# main.net
KiCad netlist of a schematic drawn in Altium Designer
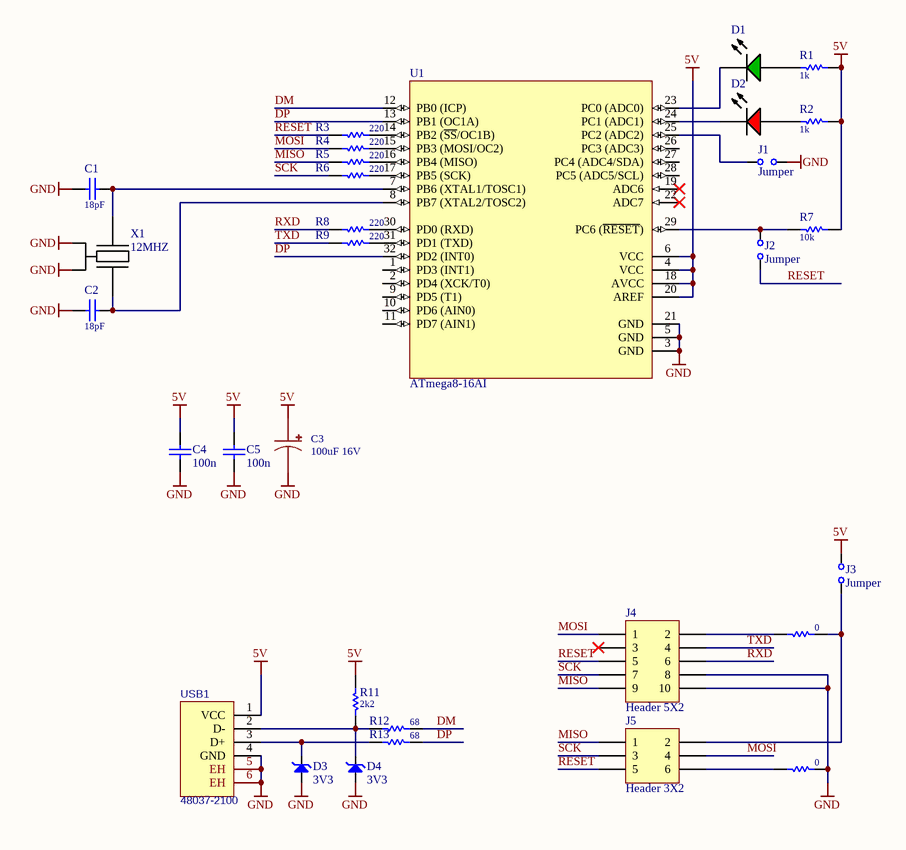
[diagram p0: main.SchDoc]

(export (version "E")
  (design (tool "Eeschema 10.0.6"))
  (components
    (comp (ref "C1")
      (value "18pF")
      (footprint "C0402")
      (description "18pF 50V 0402")
      (libsource (lib "Miscellaneous Devices") (part "CAP"))
    )
    (comp (ref "C2")
      (value "18pF")
      (footprint "C0402")
      (description "18pF 50V 0402")
      (libsource (lib "Miscellaneous Devices") (part "CAP"))
    )
    (comp (ref "C3")
      (value "100uF 16V")
      (footprint "C3528")
      (libsource (lib "altium-import") (part "root_0_mirrored_220uF_"))
    )
    (comp (ref "C4")
      (value "100n")
      (footprint "C0603")
      (libsource (lib "Miscellaneous Devices") (part "Cap"))
    )
    (comp (ref "C5")
      (value "100n")
      (footprint "C0603")
      (libsource (lib "Miscellaneous Devices") (part "Cap"))
    )
    (comp (ref "D1")
      (value "GRN")
      (footprint "LED-0603-GRN")
      (description "LED 0603 GRN")
      (libsource (lib "Miscellaneous Devices") (part "LED-0603-GREEN"))
    )
    (comp (ref "D2")
      (value "RED")
      (footprint "LED-0603-GRN")
      (libsource (lib "Schlib1") (part "LED-0603-RED"))
    )
    (comp (ref "D3")
      (value "3V3")
      (footprint "SOD-323")
      (description "SD03")
      (libsource (lib "Schlib2") (part "NCP51460SN33T1G"))
    )
    (comp (ref "D4")
      (value "3V3")
      (footprint "SOD-323")
      (description "SD03")
      (libsource (lib "Schlib2") (part "NCP51460SN33T1G"))
    )
    (comp (ref "J1") (value "Jumper") (footprint "JMP_0603") (libsource (lib "Schlib1") (part "Jumper")))
    (comp (ref "J2") (value "Jumper") (footprint "JMP_0603") (libsource (lib "Schlib1") (part "Jumper")))
    (comp (ref "J3") (value "Jumper") (footprint "JMP_0603") (libsource (lib "Schlib1") (part "Jumper")))
    (comp (ref "J4")
      (value "Header 5X2")
      (footprint "HDR_2X5")
      (description "Header, 5-Pin, Dual row")
      (libsource (lib "Miscellaneous Connectors") (part "Header 5X2"))
    )
    (comp (ref "J5")
      (value "Header 3X2")
      (footprint "HDR_2X3")
      (description "Header, 6-Pin, Dual row")
      (libsource (lib "Schlib1") (part "Header 3X2"))
    )
    (comp (ref "R1") (value "1k") (footprint "R0603") (libsource (lib "Miscellaneous Devices") (part "RES")))
    (comp (ref "R2") (value "1k") (footprint "R0603") (libsource (lib "Miscellaneous Devices") (part "RES")))
    (comp (ref "R3") (value "220") (footprint "R0805") (libsource (lib "Miscellaneous Devices") (part "RES")))
    (comp (ref "R4") (value "220") (footprint "R0603") (libsource (lib "Miscellaneous Devices") (part "RES")))
    (comp (ref "R5") (value "220") (footprint "R0603") (libsource (lib "Miscellaneous Devices") (part "RES")))
    (comp (ref "R6") (value "220") (footprint "R0603") (libsource (lib "Miscellaneous Devices") (part "RES")))
    (comp (ref "R7") (value "10k") (footprint "R0805") (libsource (lib "Miscellaneous Devices") (part "RES")))
    (comp (ref "R8")
      (value "220")
      (footprint "R0805_")
      (libsource (lib "Miscellaneous Devices") (part "RES"))
    )
    (comp (ref "R9")
      (value "220")
      (footprint "R0805_")
      (libsource (lib "Miscellaneous Devices") (part "RES"))
    )
    (comp (ref "R10") (value "0") (footprint "R0805_") (libsource (lib "Miscellaneous Devices") (part "RES")))
    (comp (ref "R11")
      (value "2k2")
      (footprint "R0603")
      (libsource (lib "Miscellaneous Devices") (part "RES"))
    )
    (comp (ref "R12") (value "68") (footprint "R0603") (libsource (lib "Miscellaneous Devices") (part "RES")))
    (comp (ref "R13") (value "68") (footprint "R0603") (libsource (lib "Miscellaneous Devices") (part "RES")))
    (comp (ref "R14") (value "0") (footprint "R0805_") (libsource (lib "Miscellaneous Devices") (part "RES")))
    (comp (ref "U1")
      (value "ATmega8-16AI")
      (footprint "32A_L")
      (description "8-Bit AVR Microcontroller with 8K Bytes of In-System Programmable Flash Memory")
      (libsource (lib "Atmel Microcontroller 8-Bit AVR") (part "ATmega8-16AI"))
    )
    (comp (ref "USB1")
      (value "48037-2100")
      (footprint "USB-A-TH_480372100")
      (libsource (lib "Schlib1") (part "48037-2100"))
    )
    (comp (ref "X1")
      (value "12MHZ")
      (footprint "CRYSTAL_2.5x2.0mm")
      (description "CRYSTAL 12MHZ 10PF SMD")
      (libsource (lib "Miscellaneous Devices") (part "CRYSTAL 12MHZ 3.20mm x 2.50mm"))
    )
  )
  (nets
    (net (code "1") (name "/DM") (class "Default")
      (node (ref "R12") (pin "2") (pinfunction "2_2") (pintype "passive"))
      (node (ref "U1") (pin "12") (pinfunction "PB0_(ICP)_12") (pintype "bidirectional"))
    )
    (net (code "2") (name "/DP") (class "Default")
      (node (ref "R13") (pin "2") (pinfunction "2_2") (pintype "passive"))
      (node (ref "U1") (pin "13") (pinfunction "PB1_(OC1A)_13") (pintype "bidirectional"))
      (node (ref "U1") (pin "32") (pinfunction "PD2_(INT0)_32") (pintype "bidirectional"))
    )
    (net (code "3") (name "/MISO") (class "Default")
      (node (ref "J4") (pin "9") (pinfunction "9_9") (pintype "passive"))
      (node (ref "J5") (pin "1") (pinfunction "1_1") (pintype "passive"))
      (node (ref "R5") (pin "2") (pinfunction "2_2") (pintype "passive"))
    )
    (net (code "4") (name "/MOSI") (class "Default")
      (node (ref "J4") (pin "1") (pinfunction "1_1") (pintype "passive"))
      (node (ref "J5") (pin "4") (pinfunction "4_4") (pintype "passive"))
      (node (ref "R4") (pin "2") (pinfunction "2_2") (pintype "passive"))
    )
    (net (code "5") (name "/RESET") (class "Default")
      (node (ref "J2") (pin "2") (pinfunction "K_2") (pintype "passive"))
      (node (ref "J4") (pin "5") (pinfunction "5_5") (pintype "passive"))
      (node (ref "J5") (pin "5") (pinfunction "5_5") (pintype "passive"))
      (node (ref "R3") (pin "2") (pinfunction "2_2") (pintype "passive"))
    )
    (net (code "6") (name "/RXD") (class "Default")
      (node (ref "J4") (pin "6") (pinfunction "6_6") (pintype "passive"))
      (node (ref "R8") (pin "2") (pinfunction "2_2") (pintype "passive"))
    )
    (net (code "7") (name "/SCK") (class "Default")
      (node (ref "J4") (pin "7") (pinfunction "7_7") (pintype "passive"))
      (node (ref "J5") (pin "3") (pinfunction "3_3") (pintype "passive"))
      (node (ref "R6") (pin "2") (pinfunction "2_2") (pintype "passive"))
    )
    (net (code "8") (name "/TXD") (class "Default")
      (node (ref "J4") (pin "4") (pinfunction "4_4") (pintype "passive"))
      (node (ref "R9") (pin "2") (pinfunction "2_2") (pintype "passive"))
    )
    (net (code "9") (name "5V") (class "Default")
      (node (ref "C3") (pin "1") (pinfunction "1_1") (pintype "passive"))
      (node (ref "C4") (pin "2") (pinfunction "2_2") (pintype "passive"))
      (node (ref "C5") (pin "2") (pinfunction "2_2") (pintype "passive"))
      (node (ref "J3") (pin "1") (pinfunction "A_1") (pintype "passive"))
      (node (ref "R1") (pin "1") (pinfunction "1_1") (pintype "passive"))
      (node (ref "R11") (pin "2") (pinfunction "2_2") (pintype "passive"))
      (node (ref "R2") (pin "1") (pinfunction "1_1") (pintype "passive"))
      (node (ref "R7") (pin "1") (pinfunction "1_1") (pintype "passive"))
      (node (ref "U1") (pin "18") (pinfunction "AVCC_18") (pintype "power_in"))
      (node (ref "U1") (pin "20") (pinfunction "AREF_20") (pintype "passive"))
      (node (ref "U1") (pin "4") (pinfunction "VCC_4") (pintype "power_in"))
      (node (ref "U1") (pin "6") (pinfunction "VCC_6") (pintype "power_in"))
      (node (ref "USB1") (pin "1") (pinfunction "VCC_1") (pintype "passive"))
    )
    (net (code "10") (name "GND") (class "Default")
      (node (ref "C1") (pin "1") (pinfunction "1_1") (pintype "passive"))
      (node (ref "C2") (pin "1") (pinfunction "1_1") (pintype "passive"))
      (node (ref "C3") (pin "2") (pinfunction "2_2") (pintype "passive"))
      (node (ref "C4") (pin "1") (pinfunction "1_1") (pintype "passive"))
      (node (ref "C5") (pin "1") (pinfunction "1_1") (pintype "passive"))
      (node (ref "D3") (pin "1") (pinfunction "-_1") (pintype "passive"))
      (node (ref "D4") (pin "1") (pinfunction "-_1") (pintype "passive"))
      (node (ref "J1") (pin "1") (pinfunction "A_1") (pintype "passive"))
      (node (ref "J4") (pin "10") (pinfunction "10_10") (pintype "passive"))
      (node (ref "J4") (pin "8") (pinfunction "8_8") (pintype "passive"))
      (node (ref "R14") (pin "1") (pinfunction "1_1") (pintype "passive"))
      (node (ref "U1") (pin "21") (pinfunction "GND_21") (pintype "power_in"))
      (node (ref "U1") (pin "3") (pinfunction "GND_3") (pintype "power_in"))
      (node (ref "U1") (pin "5") (pinfunction "GND_5") (pintype "power_in"))
      (node (ref "USB1") (pin "4") (pinfunction "GND_4") (pintype "passive"))
      (node (ref "USB1") (pin "5") (pinfunction "EH_5") (pintype "passive"))
      (node (ref "USB1") (pin "6") (pinfunction "EH_6") (pintype "passive"))
      (node (ref "X1") (pin "2") (pinfunction "GND_2") (pintype "passive"))
      (node (ref "X1") (pin "4") (pinfunction "GND_4") (pintype "passive"))
    )
    (net (code "11") (name "Net-(D1-A)") (class "Default")
      (node (ref "D1") (pin "1") (pinfunction "A_1") (pintype "passive"))
      (node (ref "R1") (pin "2") (pinfunction "2_2") (pintype "passive"))
    )
    (net (code "12") (name "Net-(D1-K)") (class "Default")
      (node (ref "D1") (pin "2") (pinfunction "K_2") (pintype "passive"))
      (node (ref "U1") (pin "23") (pinfunction "PC0_(ADC0)_23") (pintype "bidirectional"))
    )
    (net (code "13") (name "Net-(D2-A)") (class "Default")
      (node (ref "D2") (pin "1") (pinfunction "A_1") (pintype "passive"))
      (node (ref "R2") (pin "2") (pinfunction "2_2") (pintype "passive"))
    )
    (net (code "14") (name "Net-(D2-K)") (class "Default")
      (node (ref "D2") (pin "2") (pinfunction "K_2") (pintype "passive"))
      (node (ref "U1") (pin "24") (pinfunction "PC1_(ADC1)_24") (pintype "bidirectional"))
    )
    (net (code "15") (name "Net-(D3-+)") (class "Default")
      (node (ref "D3") (pin "2") (pinfunction "+_2") (pintype "passive"))
      (node (ref "R13") (pin "1") (pinfunction "1_1") (pintype "passive"))
      (node (ref "USB1") (pin "3") (pinfunction "D+_3") (pintype "passive"))
    )
    (net (code "16") (name "Net-(D4-+)") (class "Default")
      (node (ref "D4") (pin "2") (pinfunction "+_2") (pintype "passive"))
      (node (ref "R11") (pin "1") (pinfunction "1_1") (pintype "passive"))
      (node (ref "R12") (pin "1") (pinfunction "1_1") (pintype "passive"))
      (node (ref "USB1") (pin "2") (pinfunction "D-_2") (pintype "passive"))
    )
    (net (code "17") (name "Net-(J1-K)") (class "Default")
      (node (ref "J1") (pin "2") (pinfunction "K_2") (pintype "passive"))
      (node (ref "U1") (pin "25") (pinfunction "PC2_(ADC2)_25") (pintype "bidirectional"))
    )
    (net (code "18") (name "Net-(J2-A)") (class "Default")
      (node (ref "J2") (pin "1") (pinfunction "A_1") (pintype "passive"))
      (node (ref "R7") (pin "2") (pinfunction "2_2") (pintype "passive"))
      (node (ref "U1") (pin "29") (pinfunction "PC6_(~{RESET})_29") (pintype "bidirectional"))
    )
    (net (code "19") (name "Net-(J3-K)") (class "Default")
      (node (ref "J3") (pin "2") (pinfunction "K_2") (pintype "passive"))
      (node (ref "J5") (pin "2") (pinfunction "2_2") (pintype "passive"))
      (node (ref "R10") (pin "1") (pinfunction "1_1") (pintype "passive"))
    )
    (net (code "20") (name "Net-(J4-Pad2)") (class "Default")
      (node (ref "J4") (pin "2") (pinfunction "2_2") (pintype "passive"))
      (node (ref "R10") (pin "2") (pinfunction "2_2") (pintype "passive"))
    )
    (net (code "21") (name "Net-(J5-Pad6)") (class "Default")
      (node (ref "J5") (pin "6") (pinfunction "6_6") (pintype "passive"))
      (node (ref "R14") (pin "2") (pinfunction "2_2") (pintype "passive"))
    )
    (net (code "22") (name "Net-(U1-PB2_(~{SS}{slash}OC1B))") (class "Default")
      (node (ref "R3") (pin "1") (pinfunction "1_1") (pintype "passive"))
      (node (ref "U1") (pin "14") (pinfunction "PB2_(~{SS}/OC1B)_14") (pintype "bidirectional"))
    )
    (net (code "23") (name "Net-(U1-PB3_(MOSI{slash}OC2))") (class "Default")
      (node (ref "R4") (pin "1") (pinfunction "1_1") (pintype "passive"))
      (node (ref "U1") (pin "15") (pinfunction "PB3_(MOSI/OC2)_15") (pintype "bidirectional"))
    )
    (net (code "24") (name "Net-(U1-PB4_(MISO))") (class "Default")
      (node (ref "R5") (pin "1") (pinfunction "1_1") (pintype "passive"))
      (node (ref "U1") (pin "16") (pinfunction "PB4_(MISO)_16") (pintype "bidirectional"))
    )
    (net (code "25") (name "Net-(U1-PB5_(SCK))") (class "Default")
      (node (ref "R6") (pin "1") (pinfunction "1_1") (pintype "passive"))
      (node (ref "U1") (pin "17") (pinfunction "PB5_(SCK)_17") (pintype "bidirectional"))
    )
    (net (code "26") (name "Net-(U1-PB6_(XTAL1{slash}TOSC1))") (class "Default")
      (node (ref "C1") (pin "2") (pinfunction "2_2") (pintype "passive"))
      (node (ref "U1") (pin "7") (pinfunction "PB6_(XTAL1/TOSC1)_7") (pintype "bidirectional"))
      (node (ref "X1") (pin "3") (pinfunction "X2_3") (pintype "passive"))
    )
    (net (code "27") (name "Net-(U1-PB7_(XTAL2{slash}TOSC2))") (class "Default")
      (node (ref "C2") (pin "2") (pinfunction "2_2") (pintype "passive"))
      (node (ref "U1") (pin "8") (pinfunction "PB7_(XTAL2/TOSC2)_8") (pintype "bidirectional"))
      (node (ref "X1") (pin "1") (pinfunction "X1_1") (pintype "passive"))
    )
    (net (code "28") (name "Net-(U1-PD0_(RXD))") (class "Default")
      (node (ref "R8") (pin "1") (pinfunction "1_1") (pintype "passive"))
      (node (ref "U1") (pin "30") (pinfunction "PD0_(RXD)_30") (pintype "bidirectional"))
    )
    (net (code "29") (name "Net-(U1-PD1_(TXD))") (class "Default")
      (node (ref "R9") (pin "1") (pinfunction "1_1") (pintype "passive"))
      (node (ref "U1") (pin "31") (pinfunction "PD1_(TXD)_31") (pintype "bidirectional"))
    )
    (net (code "30") (name "unconnected-(J4-Pad3)") (class "Default")
      (node (ref "J4") (pin "3") (pinfunction "3_3") (pintype "passive+no_connect"))
    )
    (net (code "31") (name "unconnected-(U1-ADC6-Pad19)") (class "Default")
      (node (ref "U1") (pin "19") (pinfunction "ADC6_19") (pintype "input+no_connect"))
    )
    (net (code "32") (name "unconnected-(U1-ADC7-Pad22)") (class "Default")
      (node (ref "U1") (pin "22") (pinfunction "ADC7_22") (pintype "input+no_connect"))
    )
    (net (code "33") (name "unconnected-(U1-PC3_(ADC3)-Pad26)") (class "Default")
      (node (ref "U1") (pin "26") (pinfunction "PC3_(ADC3)_26") (pintype "bidirectional"))
    )
    (net (code "34") (name "unconnected-(U1-PC4_(ADC4{slash}SDA)-Pad27)") (class "Default")
      (node (ref "U1") (pin "27") (pinfunction "PC4_(ADC4/SDA)_27") (pintype "bidirectional"))
    )
    (net (code "35") (name "unconnected-(U1-PC5_(ADC5{slash}SCL)-Pad28)") (class "Default")
      (node (ref "U1") (pin "28") (pinfunction "PC5_(ADC5/SCL)_28") (pintype "bidirectional"))
    )
    (net (code "36") (name "unconnected-(U1-PD3_(INT1)-Pad1)") (class "Default")
      (node (ref "U1") (pin "1") (pinfunction "PD3_(INT1)_1") (pintype "bidirectional"))
    )
    (net (code "37") (name "unconnected-(U1-PD4_(XCK{slash}T0)-Pad2)") (class "Default")
      (node (ref "U1") (pin "2") (pinfunction "PD4_(XCK/T0)_2") (pintype "bidirectional"))
    )
    (net (code "38") (name "unconnected-(U1-PD5_(T1)-Pad9)") (class "Default")
      (node (ref "U1") (pin "9") (pinfunction "PD5_(T1)_9") (pintype "bidirectional"))
    )
    (net (code "39") (name "unconnected-(U1-PD6_(AIN0)-Pad10)") (class "Default")
      (node (ref "U1") (pin "10") (pinfunction "PD6_(AIN0)_10") (pintype "bidirectional"))
    )
    (net (code "40") (name "unconnected-(U1-PD7_(AIN1)-Pad11)") (class "Default")
      (node (ref "U1") (pin "11") (pinfunction "PD7_(AIN1)_11") (pintype "bidirectional"))
    )
  )
)
